# Blues_Brkr.net
KiCad netlist of a schematic drawn in Altium Designer
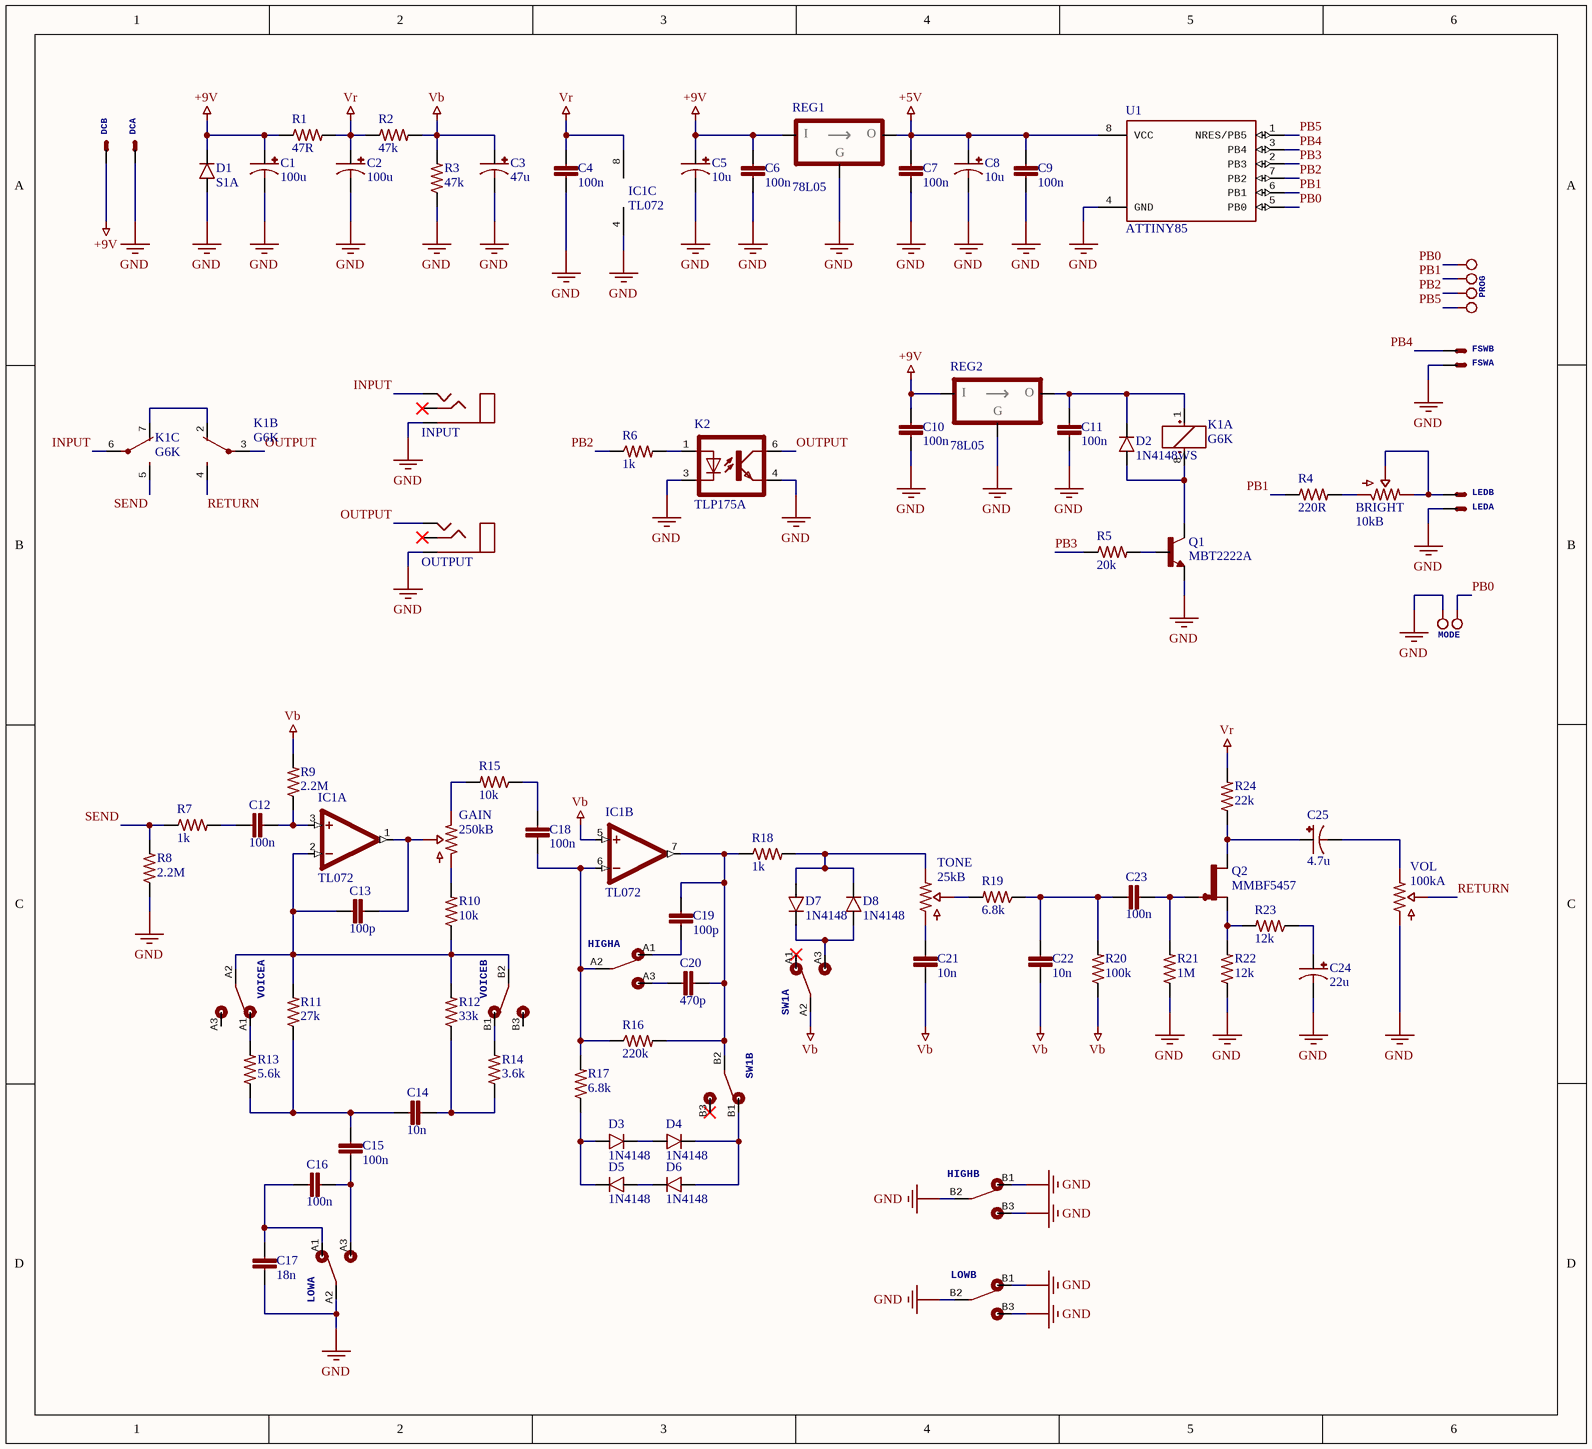
[diagram p0: Blues Brkr.SchDoc]

(export (version "E")
  (design (tool "Eeschema 10.0.6"))
  (components
    (comp (ref "BRIGHT")
      (value "10kB")
      (footprint "BOURNS_3362P")
      (description "10k Lin 3362P trimmer")
      (libsource (lib "Pedals") (part "TRIM_10kB_3362P"))
    )
    (comp (ref "C1")
      (value "100u")
      (footprint "CAPAE_D")
      (description "CAP ALUM 100UF 25V SMD")
      (fields
        (field (name "MANUFACTURER") "Multicomp")
        (field (name "MANUFACTURER PART NUMBER") "MCVVT025M101EA6L")
      )
      (libsource (lib "Pedals SMD") (part "MCVVT025M101EA6L"))
    )
    (comp (ref "C2")
      (value "100u")
      (footprint "CAPAE_D")
      (description "CAP ALUM 100UF 25V SMD")
      (fields
        (field (name "MANUFACTURER") "Multicomp")
        (field (name "MANUFACTURER PART NUMBER") "MCVVT025M101EA6L")
      )
      (libsource (lib "Pedals SMD") (part "MCVVT025M101EA6L"))
    )
    (comp (ref "C3")
      (value "47u")
      (footprint "CAPAE_D")
      (description "CAP ALUM 47UF 25V SMD")
      (fields
        (field (name "MANUFACTURER") "Multicomp")
        (field (name "MANUFACTURER PART NUMBER") "MCVVT025M470EA1L")
      )
      (libsource (lib "Pedals SMD") (part "MCVVT025M470EA1L"))
    )
    (comp (ref "C4")
      (value "100n")
      (footprint "CHIP_0603")
      (description "CAP CER 100NF 50V X7R 0603")
      (fields
        (field (name "MANUFACTURER") "Multicomp")
        (field (name "MANUFACTURER PART NUMBER") "MC0603B104K500CT")
      )
      (libsource (lib "Pedals SMD") (part "MC0603B104K500CT"))
    )
    (comp (ref "C5")
      (value "10u")
      (footprint "CAPAE_B")
      (description "CAP ALUM 10UF 25V SMD")
      (fields
        (field (name "MANUFACTURER") "Multicomp")
        (field (name "MANUFACTURER PART NUMBER") "MCVVT025M100CA1L")
      )
      (libsource (lib "Pedals SMD") (part "MCVVT025M100CA1L"))
    )
    (comp (ref "C6")
      (value "100n")
      (footprint "CHIP_0603")
      (description "CAP CER 100NF 50V X7R 0603")
      (fields
        (field (name "MANUFACTURER") "Multicomp")
        (field (name "MANUFACTURER PART NUMBER") "MC0603B104K500CT")
      )
      (libsource (lib "Pedals SMD") (part "MC0603B104K500CT"))
    )
    (comp (ref "C7")
      (value "100n")
      (footprint "CHIP_0603")
      (description "CAP CER 100NF 50V X7R 0603")
      (fields
        (field (name "MANUFACTURER") "Multicomp")
        (field (name "MANUFACTURER PART NUMBER") "MC0603B104K500CT")
      )
      (libsource (lib "Pedals SMD") (part "MC0603B104K500CT"))
    )
    (comp (ref "C8")
      (value "10u")
      (footprint "CAPAE_B")
      (description "CAP ALUM 10UF 25V SMD")
      (fields
        (field (name "MANUFACTURER") "Multicomp")
        (field (name "MANUFACTURER PART NUMBER") "MCVVT025M100CA1L")
      )
      (libsource (lib "Pedals SMD") (part "MCVVT025M100CA1L"))
    )
    (comp (ref "C9")
      (value "100n")
      (footprint "CHIP_0603")
      (description "CAP CER 100NF 50V X7R 0603")
      (fields
        (field (name "MANUFACTURER") "Multicomp")
        (field (name "MANUFACTURER PART NUMBER") "MC0603B104K500CT")
      )
      (libsource (lib "Pedals SMD") (part "MC0603B104K500CT"))
    )
    (comp (ref "C10")
      (value "100n")
      (footprint "CHIP_0603")
      (description "CAP CER 100NF 50V X7R 0603")
      (fields
        (field (name "MANUFACTURER") "Multicomp")
        (field (name "MANUFACTURER PART NUMBER") "MC0603B104K500CT")
      )
      (libsource (lib "Pedals SMD") (part "MC0603B104K500CT"))
    )
    (comp (ref "C11")
      (value "100n")
      (footprint "CHIP_0603")
      (description "CAP CER 100NF 50V X7R 0603")
      (fields
        (field (name "MANUFACTURER") "Multicomp")
        (field (name "MANUFACTURER PART NUMBER") "MC0603B104K500CT")
      )
      (libsource (lib "Pedals SMD") (part "MC0603B104K500CT"))
    )
    (comp (ref "C12")
      (value "100n")
      (footprint "CHIP_1206")
      (description "CAP CER 100NF 50V C0G/NP0 1206")
      (fields
        (field (name "MANUFACTURER") "Murata")
        (field (name "MANUFACTURER PART NUMBER") "GRM31C5C1H104JA01L")
      )
      (libsource (lib "Pedals SMD") (part "GRM31C5C1H104JA01L"))
    )
    (comp (ref "C13")
      (value "100p")
      (footprint "CHIP_0603")
      (description "CAP CER 100PF 50V C0G/NP0 0603")
      (fields
        (field (name "MANUFACTURER") "Multicomp")
        (field (name "MANUFACTURER PART NUMBER") "MC0603N101J500CT")
      )
      (libsource (lib "") (part "MC0603N101J500CT_1"))
    )
    (comp (ref "C14")
      (value "10n")
      (footprint "CHIP_0603")
      (description "CAP CER 10NF 50V C0G/NP0 0603")
      (fields
        (field (name "MANUFACTURER") "Murata")
        (field (name "MANUFACTURER PART NUMBER") "GRM1885C1H103JA01D")
      )
      (libsource (lib "Pedals SMD") (part "GRM1885C1H103JA01D"))
    )
    (comp (ref "C15")
      (value "100n")
      (footprint "CHIP_1206")
      (description "CAP CER 100NF 50V C0G/NP0 1206")
      (fields
        (field (name "MANUFACTURER") "Murata")
        (field (name "MANUFACTURER PART NUMBER") "GRM31C5C1H104JA01L")
      )
      (libsource (lib "") (part "GRM31C5C1H104JA01L_1"))
    )
    (comp (ref "C16")
      (value "100n")
      (footprint "CHIP_1206")
      (description "CAP CER 100NF 50V C0G/NP0 1206")
      (fields
        (field (name "MANUFACTURER") "Murata")
        (field (name "MANUFACTURER PART NUMBER") "GRM31C5C1H104JA01L")
      )
      (libsource (lib "") (part "GRM31C5C1H104JA01L_2"))
    )
    (comp (ref "C17")
      (value "18n")
      (footprint "CHIP_0805")
      (description "CAP CER 18NF 50V C0G/NP0 0805")
      (fields
        (field (name "MANUFACTURER") "Murata")
        (field (name "MANUFACTURER PART NUMBER") "GRM21B5C1H183JA01L")
      )
      (libsource (lib "Pedals SMD") (part "GRM21B5C1H183JA01L"))
    )
    (comp (ref "C18")
      (value "100n")
      (footprint "CHIP_1206")
      (description "CAP CER 100NF 50V C0G/NP0 1206")
      (fields
        (field (name "MANUFACTURER") "Murata")
        (field (name "MANUFACTURER PART NUMBER") "GRM31C5C1H104JA01L")
      )
      (libsource (lib "") (part "GRM31C5C1H104JA01L_1"))
    )
    (comp (ref "C19")
      (value "100p")
      (footprint "CHIP_0603")
      (description "CAP CER 100PF 50V C0G/NP0 0603")
      (fields
        (field (name "MANUFACTURER") "Multicomp")
        (field (name "MANUFACTURER PART NUMBER") "MC0603N101J500CT")
      )
      (libsource (lib "Pedals SMD") (part "MC0603N101J500CT"))
    )
    (comp (ref "C20")
      (value "470p")
      (footprint "CHIP_0603")
      (description "CAP CER 470PF 50V C0G/NP0 0603")
      (fields
        (field (name "MANUFACTURER") "Multicomp")
        (field (name "MANUFACTURER PART NUMBER") "MC0603N471J500CT")
      )
      (libsource (lib "Pedals SMD") (part "MC0603N471J500CT"))
    )
    (comp (ref "C21")
      (value "10n")
      (footprint "CHIP_0603")
      (description "CAP CER 10NF 50V C0G/NP0 0603")
      (fields
        (field (name "MANUFACTURER") "Murata")
        (field (name "MANUFACTURER PART NUMBER") "GRM1885C1H103JA01D")
      )
      (libsource (lib "") (part "GRM1885C1H103JA01D_1"))
    )
    (comp (ref "C22")
      (value "10n")
      (footprint "CHIP_0603")
      (description "CAP CER 10NF 50V C0G/NP0 0603")
      (fields
        (field (name "MANUFACTURER") "Murata")
        (field (name "MANUFACTURER PART NUMBER") "GRM1885C1H103JA01D")
      )
      (libsource (lib "") (part "GRM1885C1H103JA01D_1"))
    )
    (comp (ref "C23")
      (value "100n")
      (footprint "CHIP_1206")
      (description "CAP CER 100NF 50V C0G/NP0 1206")
      (fields
        (field (name "MANUFACTURER") "Murata")
        (field (name "MANUFACTURER PART NUMBER") "GRM31C5C1H104JA01L")
      )
      (libsource (lib "Pedals SMD") (part "GRM31C5C1H104JA01L"))
    )
    (comp (ref "C24")
      (value "22u")
      (footprint "CAPAE_D")
      (description "CAP ALUM 22UF 20% 35V LESR SMD")
      (fields
        (field (name "MANUFACTURER") "Panasonic")
        (field (name "MANUFACTURER PART NUMBER") "EEEFC1V220AP")
      )
      (libsource (lib "Pedals SMD") (part "EEEFC1V220AP"))
    )
    (comp (ref "C25")
      (value "4.7u")
      (footprint "CAPAE_C")
      (description "CAP ALUM 4.7UF 50V LESR SMD")
      (fields
        (field (name "MANUFACTURER") "Panasonic")
        (field (name "MANUFACTURER PART NUMBER") "EEEFC1H4R7R")
      )
      (libsource (lib "Pedals SMD") (part "EEEFC1H4R7R"))
    )
    (comp (ref "D1")
      (value "S1A")
      (footprint "DO214")
      (description "DIODE GEN PURP 50V 1A SMA")
      (fields (field (name "MANUFACTURER") "ON Semiconductor / Fairchild"))
      (libsource (lib "Pedals SMD") (part "S1A"))
    )
    (comp (ref "D2")
      (value "1N4148WS")
      (footprint "SOD323")
      (description "DIODE GEN PURP 75V 150MA SOD323F")
      (fields (field (name "MANUFACTURER") "ON Semiconductor / Fairchild"))
      (libsource (lib "Pedals SMD") (part "1N4148WS"))
    )
    (comp (ref "D3") (value "1N4148") (footprint "DO35_2") (libsource (lib "Pedals") (part "D_1N4148")))
    (comp (ref "D4") (value "1N4148") (footprint "DO35_2") (libsource (lib "Pedals") (part "D_1N4148")))
    (comp (ref "D5") (value "1N4148") (footprint "DO35_2") (libsource (lib "Pedals") (part "D_1N4148")))
    (comp (ref "D6") (value "1N4148") (footprint "DO35_2") (libsource (lib "Pedals") (part "D_1N4148")))
    (comp (ref "D7") (value "1N4148") (footprint "DO35_2") (libsource (lib "Pedals") (part "D_1N4148")))
    (comp (ref "D8") (value "1N4148") (footprint "DO35_2") (libsource (lib "Pedals") (part "D_1N4148")))
    (comp (ref "DC")
      (value "J_JST-XH-02")
      (footprint "JST-XH-02")
      (description "2 Pins male XH header")
      (libsource (lib "Pedals") (part "J_JST-XH-02"))
    )
    (comp (ref "FSW")
      (value "~")
      (footprint "JST-XH-02")
      (description "2 Pins male XH header")
      (libsource (lib "Pedals") (part "JST-XH-02"))
    )
    (comp (ref "GAIN")
      (value "250kB")
      (footprint "ALPHA_16mm_BOTTOM")
      (description "250k Lin potentiometer round shaft")
      (libsource (lib "Pedals") (part "250kB_ALPHA_16mm"))
    )
    (comp (ref "HIGH")
      (value "DPDT")
      (footprint "DPDT_SLIDE")
      (description "DPDT slide switch ON/OFF/ON")
      (libsource (lib "Pedals") (part "SW_SLIDE_DPDT_ON-OFF-ON"))
    )
    (comp (ref "IC1")
      (value "TL072")
      (footprint "SO-8")
      (description "IC OPAMP JFET 4MHZ 8SO")
      (fields
        (field (name "MANUFACTURER") "STMicroelectronics")
        (field (name "MANUFACTURER PART NUMBER") "TL072CDT")
      )
      (libsource (lib "Pedals SMD") (part "TL072CDT"))
    )
    (comp (ref "INPUT")
      (value "~")
      (footprint "STEREO")
      (description "6.35mm stereo insulated socket jack PCB mounted")
      (libsource (lib "Pedals") (part "STEREO"))
    )
    (comp (ref "K1")
      (value "G6K")
      (footprint "G6K")
      (description "OMRON - G6K-2F 5DC - RELAY, SIGNAL, DPDT, 30VDC, 1A")
      (fields (field (name "MANUFACTURER") "Cliff") (field (name "MANUFACTURER PART NUMBER") "G6K-2F5DC"))
      (libsource (lib "Pedals SMD") (part "G6K-2F5DC"))
    )
    (comp (ref "K2")
      (value "TLP175A")
      (footprint "TLP175A")
      (description "Toshiba TLP175A AC Input MOSFET Output Optocoupler, Surface Mount, 4-Pin SOIC")
      (fields (field (name "MANUFACTURER") "Toshiba"))
      (libsource (lib "Pedals SMD") (part "TLP175A"))
    )
    (comp (ref "LED")
      (value "~")
      (footprint "JST-XH-02")
      (description "2 Pins male XH header")
      (libsource (lib "Pedals") (part "JST-XH-02"))
    )
    (comp (ref "LOW")
      (value "DPDT")
      (footprint "DPDT_SLIDE")
      (description "DPDT slide switch ON/OFF/ON")
      (libsource (lib "Pedals") (part "SW_SLIDE_DPDT_ON-OFF-ON"))
    )
    (comp (ref "MODE")
      (value "HEADER_2PINS")
      (footprint "HEADER_2PINS")
      (description "2 Pins male header")
      (libsource (lib "Pedals") (part "HEADER_2PINS"))
    )
    (comp (ref "OUTPUT")
      (value "~")
      (footprint "STEREO")
      (description "6.35mm stereo insulated socket jack PCB mounted")
      (libsource (lib "Pedals") (part "STEREO"))
    )
    (comp (ref "PROG")
      (value "J_HEADER_4PINS_FEM")
      (footprint "HEADER_4Pins_FEM")
      (description "4 Pins female header")
      (libsource (lib "Pedals") (part "J_HEADER_4PINS_FEM"))
    )
    (comp (ref "Q1")
      (value "MBT2222A")
      (footprint "SOT323")
      (description "TRANS NPN 40V 0.6A SOT323")
      (fields
        (field (name "MANUFACTURER") "ON Semiconductor")
        (field (name "MANUFACTURER PART NUMBER") "MMBT2222AWT1G")
      )
      (libsource (lib "Pedals SMD") (part "MMBT2222AWT1G"))
    )
    (comp (ref "Q2")
      (value "MMBF5457")
      (footprint "SOT23")
      (description "JFET N-CH 25V 350MW SOT23")
      (fields (field (name "MANUFACTURER") "ON Semiconductor / Fairchild"))
      (libsource (lib "Pedals SMD") (part "MMBF5457"))
    )
    (comp (ref "R1")
      (value "47R")
      (footprint "CHIP_R_1206")
      (description "RES SMD 47 OHM 1% 1/4W 1206")
      (fields
        (field (name "MANUFACTURER") "Vishay")
        (field (name "MANUFACTURER PART NUMBER") "CRCW120647R0FKEA")
      )
      (libsource (lib "Pedals SMD") (part "CRCW120647R0FKEA"))
    )
    (comp (ref "R2")
      (value "47k")
      (footprint "CHIP_R_1206")
      (description "RES SMD 47K OHM 1% 1/4W 1206")
      (fields
        (field (name "MANUFACTURER") "Vishay")
        (field (name "MANUFACTURER PART NUMBER") "CRCW120647K0FKEA")
      )
      (libsource (lib "Pedals SMD") (part "CRCW120647K0FKEA"))
    )
    (comp (ref "R3")
      (value "47k")
      (footprint "CHIP_R_1206")
      (description "RES SMD 47K OHM 1% 1/4W 1206")
      (fields
        (field (name "MANUFACTURER") "Vishay")
        (field (name "MANUFACTURER PART NUMBER") "CRCW120647K0FKEA")
      )
      (libsource (lib "Pedals SMD") (part "CRCW120647K0FKEA"))
    )
    (comp (ref "R4")
      (value "220R")
      (footprint "CHIP_R_1206")
      (description "RES SMD 220 OHM 1% 1/4W 1206")
      (fields
        (field (name "MANUFACTURER") "Vishay")
        (field (name "MANUFACTURER PART NUMBER") "CRCW1206220RFKEA")
      )
      (libsource (lib "Pedals SMD") (part "CRCW1206220RFKEA"))
    )
    (comp (ref "R5")
      (value "20k")
      (footprint "CHIP_R_0603")
      (description "RES SMD 20K OHM 1% 1/10W 0603")
      (fields
        (field (name "MANUFACTURER") "Vishay")
        (field (name "MANUFACTURER PART NUMBER") "CRCW060320K0FKEA")
      )
      (libsource (lib "Pedals SMD") (part "CRCW060320K0FKEA"))
    )
    (comp (ref "R6")
      (value "1k")
      (footprint "CHIP_R_0603")
      (description "RES SMD 1K OHM 1% 1/10W 0603")
      (fields
        (field (name "MANUFACTURER") "Vishay Dale")
        (field (name "MANUFACTURER PART NUMBER") "CRCW06031K00FKEA")
      )
      (libsource (lib "Pedals SMD") (part "CRCW06031K00FKEA"))
    )
    (comp (ref "R7")
      (value "1k")
      (footprint "CHIP_R_0603")
      (description "RES SMD 1K OHM 1% 1/10W 0603")
      (fields
        (field (name "MANUFACTURER") "Vishay Dale")
        (field (name "MANUFACTURER PART NUMBER") "CRCW06031K00FKEA")
      )
      (libsource (lib "Pedals SMD") (part "CRCW06031K00FKEA"))
    )
    (comp (ref "R8")
      (value "2.2M")
      (footprint "CHIP_R_0603")
      (description "RES SMD 2.2M OHM 1% 1/10W 0603")
      (fields
        (field (name "MANUFACTURER") "Vishay")
        (field (name "MANUFACTURER PART NUMBER") "CRCW06032M20FKEA")
      )
      (libsource (lib "Pedals SMD") (part "CRCW06032M20FKEA"))
    )
    (comp (ref "R9")
      (value "2.2M")
      (footprint "CHIP_R_0603")
      (description "RES SMD 2.2M OHM 1% 1/10W 0603")
      (fields
        (field (name "MANUFACTURER") "Vishay")
        (field (name "MANUFACTURER PART NUMBER") "CRCW06032M20FKEA")
      )
      (libsource (lib "Pedals SMD") (part "CRCW06032M20FKEA"))
    )
    (comp (ref "R10")
      (value "10k")
      (footprint "CHIP_R_0603")
      (description "RES SMD 10K OHM 1% 1/10W 0603")
      (fields
        (field (name "MANUFACTURER") "Vishay")
        (field (name "MANUFACTURER PART NUMBER") "CRCW060310K0FKEA")
      )
      (libsource (lib "Pedals SMD") (part "CRCW060310K0FKEA"))
    )
    (comp (ref "R11")
      (value "27k")
      (footprint "CHIP_R_0603")
      (description "RES SMD 27K OHM 1% 1/10W 0603")
      (fields
        (field (name "MANUFACTURER") "Vishay")
        (field (name "MANUFACTURER PART NUMBER") "CRCW060327K0FKEA")
      )
      (libsource (lib "Pedals SMD") (part "CRCW060327K0FKEA"))
    )
    (comp (ref "R12")
      (value "33k")
      (footprint "CHIP_R_0603")
      (description "RES SMD 33K OHM 1% 1/10W 0603")
      (fields
        (field (name "MANUFACTURER") "Vishay")
        (field (name "MANUFACTURER PART NUMBER") "CRCW060333K0FKEA")
      )
      (libsource (lib "Pedals SMD") (part "CRCW060333K0FKEA"))
    )
    (comp (ref "R13")
      (value "5.6k")
      (footprint "CHIP_R_0603")
      (description "RES SMD 5.6K OHM 1% 1/10W 0603")
      (fields
        (field (name "MANUFACTURER") "Vishay")
        (field (name "MANUFACTURER PART NUMBER") "CRCW06035K60FKEA")
      )
      (libsource (lib "Pedals SMD") (part "CRCW06035K60FKEA"))
    )
    (comp (ref "R14")
      (value "3.6k")
      (footprint "CHIP_R_0603")
      (description "RES SMD 3.6K OHM 1% 1/10W 0603")
      (fields
        (field (name "MANUFACTURER") "Vishay")
        (field (name "MANUFACTURER PART NUMBER") "CRCW06033K60FKEA")
      )
      (libsource (lib "Pedals SMD") (part "CRCW06033K60FKEA"))
    )
    (comp (ref "R15")
      (value "10k")
      (footprint "CHIP_R_0603")
      (description "RES SMD 10K OHM 1% 1/10W 0603")
      (fields
        (field (name "MANUFACTURER") "Vishay")
        (field (name "MANUFACTURER PART NUMBER") "CRCW060310K0FKEA")
      )
      (libsource (lib "Pedals SMD") (part "CRCW060310K0FKEA"))
    )
    (comp (ref "R16")
      (value "220k")
      (footprint "CHIP_R_0603")
      (description "RES SMD 220K OHM 1% 1/10W 0603")
      (fields
        (field (name "MANUFACTURER") "Vishay")
        (field (name "MANUFACTURER PART NUMBER") "CRCW0603220KFKEA")
      )
      (libsource (lib "Pedals SMD") (part "CRCW0603220KFKEA"))
    )
    (comp (ref "R17")
      (value "6.8k")
      (footprint "CHIP_R_0603")
      (description "RES SMD 6.8K OHM 1% 1/10W 0603")
      (fields
        (field (name "MANUFACTURER") "Vishay")
        (field (name "MANUFACTURER PART NUMBER") "CRCW06036K80FKEA")
      )
      (libsource (lib "Pedals SMD") (part "CRCW06036K80FKEA"))
    )
    (comp (ref "R18")
      (value "1k")
      (footprint "CHIP_R_0603")
      (description "RES SMD 1K OHM 1% 1/10W 0603")
      (fields
        (field (name "MANUFACTURER") "Vishay Dale")
        (field (name "MANUFACTURER PART NUMBER") "CRCW06031K00FKEA")
      )
      (libsource (lib "Pedals SMD") (part "CRCW06031K00FKEA"))
    )
    (comp (ref "R19")
      (value "6.8k")
      (footprint "CHIP_R_0603")
      (description "RES SMD 6.8K OHM 1% 1/10W 0603")
      (fields
        (field (name "MANUFACTURER") "Vishay")
        (field (name "MANUFACTURER PART NUMBER") "CRCW06036K80FKEA")
      )
      (libsource (lib "Pedals SMD") (part "CRCW06036K80FKEA"))
    )
    (comp (ref "R20")
      (value "100k")
      (footprint "CHIP_R_0603")
      (description "RES SMD 100K OHM 1% 1/10W 0603")
      (fields
        (field (name "MANUFACTURER") "Vishay")
        (field (name "MANUFACTURER PART NUMBER") "CRCW0603100KFKEA")
      )
      (libsource (lib "Pedals SMD") (part "CRCW0603100KFKEA"))
    )
    (comp (ref "R21")
      (value "1M")
      (footprint "CHIP_R_0603")
      (description "RES SMD 1M OHM 1% 1/10W 0603")
      (fields
        (field (name "MANUFACTURER") "Vishay")
        (field (name "MANUFACTURER PART NUMBER") "CRCW06031M00FKEA")
      )
      (libsource (lib "Pedals SMD") (part "CRCW06031M00FKEA"))
    )
    (comp (ref "R22")
      (value "12k")
      (footprint "CHIP_R_0603")
      (description "RES SMD 12K OHM 1% 1/10W 0603")
      (fields
        (field (name "MANUFACTURER") "Vishay")
        (field (name "MANUFACTURER PART NUMBER") "CRCW060312K0FKEA")
      )
      (libsource (lib "Pedals SMD") (part "CRCW060312K0FKEA"))
    )
    (comp (ref "R23")
      (value "12k")
      (footprint "CHIP_R_0603")
      (description "RES SMD 12K OHM 1% 1/10W 0603")
      (fields
        (field (name "MANUFACTURER") "Vishay")
        (field (name "MANUFACTURER PART NUMBER") "CRCW060312K0FKEA")
      )
      (libsource (lib "Pedals SMD") (part "CRCW060312K0FKEA"))
    )
    (comp (ref "R24")
      (value "22k")
      (footprint "CHIP_R_0603")
      (description "RES SMD 22K OHM 1% 1/10W 0603")
      (fields
        (field (name "MANUFACTURER") "Vishay")
        (field (name "MANUFACTURER PART NUMBER") "CRCW060322K0FKEA")
      )
      (libsource (lib "Pedals SMD") (part "CRCW060322K0FKEA"))
    )
    (comp (ref "REG1")
      (value "78L05")
      (footprint "SOT23-3")
      (description "TAIWAN SEMICONDUCTOR - TS78L05CX RFG - REG 3-TERMINAL 100MA, SMD, SOT23-3")
      (fields
        (field (name "MANUFACTURER") "Taiwan Semiconductor")
        (field (name "MANUFACTURER PART NUMBER") "TS78L05CXRFG")
      )
      (libsource (lib "Pedals SMD") (part "TS78L05CXRFG"))
    )
    (comp (ref "REG2")
      (value "78L05")
      (footprint "SOT23-3")
      (description "TAIWAN SEMICONDUCTOR - TS78L05CX RFG - REG 3-TERMINAL 100MA, SMD, SOT23-3")
      (fields
        (field (name "MANUFACTURER") "Taiwan Semiconductor")
        (field (name "MANUFACTURER PART NUMBER") "TS78L05CXRFG")
      )
      (libsource (lib "Pedals SMD") (part "TS78L05CXRFG"))
    )
    (comp (ref "SW1")
      (value "DPDT")
      (footprint "DPDT")
      (description "DPDT toggle switch ON/OFF/ON")
      (libsource (lib "Pedals") (part "DPDT_ON-OFF-ON"))
    )
    (comp (ref "TONE")
      (value "25kB")
      (footprint "ALPHA_16mm_BOTTOM")
      (description "25k Lin potentiometer round shaft")
      (libsource (lib "Pedals") (part "25kB_ALPHA_16mm"))
    )
    (comp (ref "U1")
      (value "ATTINY85")
      (footprint "SOP8")
      (description "IC, 8BIT MCU, AVR TINY, 20MHZ, 8-SOIC")
      (fields
        (field (name "MANUFACTURER") "Microchip / Atmel")
        (field (name "MANUFACTURER PART NUMBER") "ATTINY85-20SU")
      )
      (libsource (lib "Pedals SMD") (part "ATTINY85-20SU"))
    )
    (comp (ref "VOICE")
      (value "DPDT")
      (footprint "DPDT_SLIDE")
      (description "DPDT slide switch ON/ON")
      (libsource (lib "") (part "SW_SLIDE_DPDT_ON-ON_1"))
    )
    (comp (ref "VOL")
      (value "100kA")
      (footprint "ALPHA_16mm_BOTTOM")
      (description "100k Log potentiometer round shaft")
      (libsource (lib "Pedals") (part "100kA_ALPHA_16mm"))
    )
  )
  (nets
    (net (code "1") (name "+5V") (class "Default")
      (node (ref "C7") (pin "1") (pinfunction "1_1") (pintype "passive"))
      (node (ref "C8") (pin "+") (pinfunction "+_+") (pintype "passive"))
      (node (ref "C9") (pin "1") (pinfunction "1_1") (pintype "passive"))
      (node (ref "REG1") (pin "1") (pinfunction "OUTPUT_1") (pintype "power_in"))
      (node (ref "U1") (pin "8") (pinfunction "VCC_8") (pintype "power_in"))
    )
    (net (code "2") (name "+9V") (class "Default")
      (node (ref "C1") (pin "+") (pinfunction "+_+") (pintype "passive"))
      (node (ref "C10") (pin "1") (pinfunction "1_1") (pintype "passive"))
      (node (ref "C5") (pin "+") (pinfunction "+_+") (pintype "passive"))
      (node (ref "C6") (pin "1") (pinfunction "1_1") (pintype "passive"))
      (node (ref "D1") (pin "1") (pinfunction "1_1") (pintype "passive"))
      (node (ref "DC") (pin "1") (pinfunction "S_1") (pintype "passive"))
      (node (ref "R1") (pin "1") (pinfunction "1_1") (pintype "passive"))
      (node (ref "REG1") (pin "2") (pinfunction "INPUT_2") (pintype "power_in"))
      (node (ref "REG2") (pin "2") (pinfunction "INPUT_2") (pintype "power_in"))
    )
    (net (code "3") (name "/INPUT") (class "Default")
      (node (ref "INPUT") (pin "T") (pinfunction "T_T") (pintype "passive"))
      (node (ref "K1") (pin "6") (pinfunction "P_6") (pintype "passive"))
    )
    (net (code "4") (name "/OUTPUT") (class "Default")
      (node (ref "K1") (pin "3") (pinfunction "P_3") (pintype "passive"))
      (node (ref "K2") (pin "6") (pinfunction "COL_6") (pintype "passive"))
      (node (ref "OUTPUT") (pin "T") (pinfunction "T_T") (pintype "passive"))
    )
    (net (code "5") (name "/PB0") (class "Default")
      (node (ref "MODE") (pin "2") (pinfunction "2_2") (pintype "passive"))
      (node (ref "PROG") (pin "4") (pinfunction "4_4") (pintype "passive"))
      (node (ref "U1") (pin "5") (pinfunction "PB0_5") (pintype "bidirectional"))
    )
    (net (code "6") (name "/PB1") (class "Default")
      (node (ref "PROG") (pin "3") (pinfunction "3_3") (pintype "passive"))
      (node (ref "R4") (pin "1") (pinfunction "1_1") (pintype "passive"))
      (node (ref "U1") (pin "6") (pinfunction "PB1_6") (pintype "bidirectional"))
    )
    (net (code "7") (name "/PB2") (class "Default")
      (node (ref "PROG") (pin "2") (pinfunction "2_2") (pintype "passive"))
      (node (ref "R6") (pin "1") (pinfunction "1_1") (pintype "passive"))
      (node (ref "U1") (pin "7") (pinfunction "PB2_7") (pintype "bidirectional"))
    )
    (net (code "8") (name "/PB3") (class "Default")
      (node (ref "R5") (pin "1") (pinfunction "1_1") (pintype "passive"))
      (node (ref "U1") (pin "2") (pinfunction "PB3_2") (pintype "bidirectional"))
    )
    (net (code "9") (name "/PB4") (class "Default")
      (node (ref "FSW") (pin "1") (pinfunction "S_1") (pintype "passive"))
      (node (ref "U1") (pin "3") (pinfunction "PB4_3") (pintype "bidirectional"))
    )
    (net (code "10") (name "/PB5") (class "Default")
      (node (ref "PROG") (pin "1") (pinfunction "1_1") (pintype "passive"))
      (node (ref "U1") (pin "1") (pinfunction "NRES/PB5_1") (pintype "bidirectional"))
    )
    (net (code "11") (name "/RETURN") (class "Default")
      (node (ref "K1") (pin "4") (pinfunction "S_4") (pintype "passive"))
      (node (ref "VOL") (pin "2") (pinfunction "2_2") (pintype "passive"))
    )
    (net (code "12") (name "/SEND") (class "Default")
      (node (ref "K1") (pin "5") (pinfunction "S_5") (pintype "passive"))
      (node (ref "R7") (pin "1") (pinfunction "1_1") (pintype "passive"))
      (node (ref "R8") (pin "2") (pinfunction "2_2") (pintype "passive"))
    )
    (net (code "13") (name "GND") (class "Default")
      (node (ref "C1") (pin "-") (pinfunction "-_-") (pintype "passive"))
      (node (ref "C10") (pin "2") (pinfunction "2_2") (pintype "passive"))
      (node (ref "C11") (pin "2") (pinfunction "2_2") (pintype "passive"))
      (node (ref "C17") (pin "2") (pinfunction "2_2") (pintype "passive"))
      (node (ref "C2") (pin "-") (pinfunction "-_-") (pintype "passive"))
      (node (ref "C24") (pin "-") (pinfunction "-_-") (pintype "passive"))
      (node (ref "C3") (pin "-") (pinfunction "-_-") (pintype "passive"))
      (node (ref "C4") (pin "2") (pinfunction "2_2") (pintype "passive"))
      (node (ref "C5") (pin "-") (pinfunction "-_-") (pintype "passive"))
      (node (ref "C6") (pin "2") (pinfunction "2_2") (pintype "passive"))
      (node (ref "C7") (pin "2") (pinfunction "2_2") (pintype "passive"))
      (node (ref "C8") (pin "-") (pinfunction "-_-") (pintype "passive"))
      (node (ref "C9") (pin "2") (pinfunction "2_2") (pintype "passive"))
      (node (ref "D1") (pin "2") (pinfunction "2_2") (pintype "passive"))
      (node (ref "DC") (pin "2") (pinfunction "S_2") (pintype "passive"))
      (node (ref "FSW") (pin "2") (pinfunction "S_2") (pintype "passive"))
      (node (ref "HIGH") (pin "B1") (pinfunction "1_B1") (pintype "passive"))
      (node (ref "HIGH") (pin "B2") (pinfunction "2_B2") (pintype "passive"))
      (node (ref "HIGH") (pin "B3") (pinfunction "3_B3") (pintype "passive"))
      (node (ref "IC1") (pin "4") (pinfunction "V-_4") (pintype "power_in"))
      (node (ref "INPUT") (pin "S") (pinfunction "S_S") (pintype "passive"))
      (node (ref "K2") (pin "3") (pinfunction "C_3") (pintype "passive"))
      (node (ref "K2") (pin "4") (pinfunction "EMIT_4") (pintype "passive"))
      (node (ref "LED") (pin "2") (pinfunction "S_2") (pintype "passive"))
      (node (ref "LOW") (pin "A2") (pinfunction "2_A2") (pintype "passive"))
      (node (ref "LOW") (pin "B1") (pinfunction "1_B1") (pintype "passive"))
      (node (ref "LOW") (pin "B2") (pinfunction "2_B2") (pintype "passive"))
      (node (ref "LOW") (pin "B3") (pinfunction "3_B3") (pintype "passive"))
      (node (ref "MODE") (pin "1") (pinfunction "1_1") (pintype "passive"))
      (node (ref "OUTPUT") (pin "S") (pinfunction "S_S") (pintype "passive"))
      (node (ref "Q1") (pin "2") (pinfunction "E_2") (pintype "passive"))
      (node (ref "R21") (pin "1") (pinfunction "1_1") (pintype "passive"))
      (node (ref "R22") (pin "1") (pinfunction "1_1") (pintype "passive"))
      (node (ref "R3") (pin "1") (pinfunction "1_1") (pintype "passive"))
      (node (ref "R8") (pin "1") (pinfunction "1_1") (pintype "passive"))
      (node (ref "REG1") (pin "3") (pinfunction "COMMON_3") (pintype "power_in"))
      (node (ref "REG2") (pin "3") (pinfunction "COMMON_3") (pintype "power_in"))
      (node (ref "U1") (pin "4") (pinfunction "GND_4") (pintype "power_in"))
      (node (ref "VOL") (pin "1") (pinfunction "1_1") (pintype "passive"))
    )
    (net (code "14") (name "Net-(BRIGHT-Pad1)") (class "Default")
      (node (ref "BRIGHT") (pin "1") (pinfunction "1_1") (pintype "passive"))
      (node (ref "R4") (pin "2") (pinfunction "2_2") (pintype "passive"))
    )
    (net (code "15") (name "Net-(C12-Pad2)") (class "Default")
      (node (ref "C12") (pin "2") (pinfunction "2_2") (pintype "passive"))
      (node (ref "R7") (pin "2") (pinfunction "2_2") (pintype "passive"))
    )
    (net (code "16") (name "Net-(C14-Pad1)") (class "Default")
      (node (ref "C14") (pin "1") (pinfunction "1_1") (pintype "passive"))
      (node (ref "R12") (pin "1") (pinfunction "1_1") (pintype "passive"))
      (node (ref "R14") (pin "1") (pinfunction "1_1") (pintype "passive"))
    )
    (net (code "17") (name "Net-(C14-Pad2)") (class "Default")
      (node (ref "C14") (pin "2") (pinfunction "2_2") (pintype "passive"))
      (node (ref "C15") (pin "1") (pinfunction "1_1") (pintype "passive"))
      (node (ref "R11") (pin "1") (pinfunction "1_1") (pintype "passive"))
      (node (ref "R13") (pin "1") (pinfunction "1_1") (pintype "passive"))
    )
    (net (code "18") (name "Net-(C18-Pad1)") (class "Default")
      (node (ref "C18") (pin "1") (pinfunction "1_1") (pintype "passive"))
      (node (ref "R15") (pin "1") (pinfunction "1_1") (pintype "passive"))
    )
    (net (code "19") (name "Net-(C21-Pad1)") (class "Default")
      (node (ref "C21") (pin "1") (pinfunction "1_1") (pintype "passive"))
      (node (ref "TONE") (pin "1") (pinfunction "1_1") (pintype "passive"))
    )
    (net (code "20") (name "Net-(C22-Pad1)") (class "Default")
      (node (ref "C22") (pin "1") (pinfunction "1_1") (pintype "passive"))
      (node (ref "C23") (pin "2") (pinfunction "2_2") (pintype "passive"))
      (node (ref "R19") (pin "1") (pinfunction "1_1") (pintype "passive"))
      (node (ref "R20") (pin "2") (pinfunction "2_2") (pintype "passive"))
    )
    (net (code "21") (name "Net-(C24-Pad+)") (class "Default")
      (node (ref "C24") (pin "+") (pinfunction "+_+") (pintype "passive"))
      (node (ref "R23") (pin "1") (pinfunction "1_1") (pintype "passive"))
    )
    (net (code "22") (name "Net-(C25-Pad-)") (class "Default")
      (node (ref "C25") (pin "-") (pinfunction "-_-") (pintype "passive"))
      (node (ref "VOL") (pin "3") (pinfunction "3_3") (pintype "passive"))
    )
    (net (code "23") (name "Net-(D3-PadA)") (class "Default")
      (node (ref "D3") (pin "A") (pinfunction "A_A") (pintype "passive"))
      (node (ref "D5") (pin "C") (pinfunction "C_C") (pintype "passive"))
      (node (ref "R17") (pin "1") (pinfunction "1_1") (pintype "passive"))
    )
    (net (code "24") (name "Net-(D3-PadC)") (class "Default")
      (node (ref "D3") (pin "C") (pinfunction "C_C") (pintype "passive"))
      (node (ref "D4") (pin "A") (pinfunction "A_A") (pintype "passive"))
    )
    (net (code "25") (name "Net-(D5-PadA)") (class "Default")
      (node (ref "D5") (pin "A") (pinfunction "A_A") (pintype "passive"))
      (node (ref "D6") (pin "C") (pinfunction "C_C") (pintype "passive"))
    )
    (net (code "26") (name "Net-(D7-PadA)") (class "Default")
      (node (ref "D7") (pin "A") (pinfunction "A_A") (pintype "passive"))
      (node (ref "D8") (pin "C") (pinfunction "C_C") (pintype "passive"))
      (node (ref "R18") (pin "2") (pinfunction "2_2") (pintype "passive"))
      (node (ref "TONE") (pin "3") (pinfunction "3_3") (pintype "passive"))
    )
    (net (code "27") (name "Net-(GAIN-Pad1)") (class "Default")
      (node (ref "GAIN") (pin "1") (pinfunction "1_1") (pintype "passive"))
      (node (ref "R10") (pin "2") (pinfunction "2_2") (pintype "passive"))
    )
    (net (code "28") (name "Net-(GAIN-Pad3)") (class "Default")
      (node (ref "GAIN") (pin "3") (pinfunction "3_3") (pintype "passive"))
      (node (ref "R15") (pin "2") (pinfunction "2_2") (pintype "passive"))
    )
    (net (code "29") (name "Net-(HIGHA-1)") (class "Default")
      (node (ref "C19") (pin "2") (pinfunction "2_2") (pintype "passive"))
      (node (ref "HIGH") (pin "A1") (pinfunction "1_A1") (pintype "passive"))
    )
    (net (code "30") (name "Net-(HIGHA-2)") (class "Default")
      (node (ref "C18") (pin "2") (pinfunction "2_2") (pintype "passive"))
      (node (ref "HIGH") (pin "A2") (pinfunction "2_A2") (pintype "passive"))
      (node (ref "IC1") (pin "6") (pinfunction "-IN_6") (pintype "input"))
      (node (ref "R16") (pin "1") (pinfunction "1_1") (pintype "passive"))
      (node (ref "R17") (pin "2") (pinfunction "2_2") (pintype "passive"))
    )
    (net (code "31") (name "Net-(HIGHA-3)") (class "Default")
      (node (ref "C20") (pin "2") (pinfunction "2_2") (pintype "passive"))
      (node (ref "HIGH") (pin "A3") (pinfunction "3_A3") (pintype "passive"))
    )
    (net (code "32") (name "Net-(IC1A-+IN)") (class "Default")
      (node (ref "C12") (pin "1") (pinfunction "1_1") (pintype "passive"))
      (node (ref "IC1") (pin "3") (pinfunction "+IN_3") (pintype "input"))
      (node (ref "R9") (pin "1") (pinfunction "1_1") (pintype "passive"))
    )
    (net (code "33") (name "Net-(IC1A--IN)") (class "Default")
      (node (ref "C13") (pin "2") (pinfunction "2_2") (pintype "passive"))
      (node (ref "IC1") (pin "2") (pinfunction "-IN_2") (pintype "input"))
      (node (ref "R10") (pin "1") (pinfunction "1_1") (pintype "passive"))
      (node (ref "R11") (pin "2") (pinfunction "2_2") (pintype "passive"))
      (node (ref "R12") (pin "2") (pinfunction "2_2") (pintype "passive"))
      (node (ref "VOICE") (pin "A2") (pinfunction "2_A2") (pintype "passive"))
      (node (ref "VOICE") (pin "B2") (pinfunction "2_B2") (pintype "passive"))
    )
    (net (code "34") (name "Net-(IC1A-OUT)") (class "Default")
      (node (ref "C13") (pin "1") (pinfunction "1_1") (pintype "passive"))
      (node (ref "GAIN") (pin "2") (pinfunction "2_2") (pintype "passive"))
      (node (ref "IC1") (pin "1") (pinfunction "OUT_1") (pintype "output"))
    )
    (net (code "35") (name "Net-(IC1B-OUT)") (class "Default")
      (node (ref "C19") (pin "1") (pinfunction "1_1") (pintype "passive"))
      (node (ref "C20") (pin "1") (pinfunction "1_1") (pintype "passive"))
      (node (ref "IC1") (pin "7") (pinfunction "OUT_7") (pintype "output"))
      (node (ref "R16") (pin "2") (pinfunction "2_2") (pintype "passive"))
      (node (ref "R18") (pin "1") (pinfunction "1_1") (pintype "passive"))
      (node (ref "SW1") (pin "B2") (pinfunction "2_B2") (pintype "passive"))
    )
    (net (code "36") (name "Net-(K1A-+)") (class "Default")
      (node (ref "C11") (pin "1") (pinfunction "1_1") (pintype "passive"))
      (node (ref "D2") (pin "1") (pinfunction "1_1") (pintype "passive"))
      (node (ref "K1") (pin "1") (pinfunction "+_1") (pintype "passive"))
      (node (ref "REG2") (pin "1") (pinfunction "OUTPUT_1") (pintype "power_in"))
    )
    (net (code "37") (name "Net-(K1A--)") (class "Default")
      (node (ref "D2") (pin "2") (pinfunction "2_2") (pintype "passive"))
      (node (ref "K1") (pin "8") (pinfunction "-_8") (pintype "passive"))
      (node (ref "Q1") (pin "3") (pinfunction "C_3") (pintype "passive"))
    )
    (net (code "38") (name "Net-(K1B-O)") (class "Default")
      (node (ref "K1") (pin "2") (pinfunction "O_2") (pintype "passive"))
      (node (ref "K1") (pin "7") (pinfunction "O_7") (pintype "passive"))
    )
    (net (code "39") (name "Net-(K2-A)") (class "Default")
      (node (ref "K2") (pin "1") (pinfunction "A_1") (pintype "passive"))
      (node (ref "R6") (pin "2") (pinfunction "2_2") (pintype "passive"))
    )
    (net (code "40") (name "Net-(LEDB-S)") (class "Default")
      (node (ref "BRIGHT") (pin "2") (pinfunction "2_2") (pintype "passive"))
      (node (ref "BRIGHT") (pin "3") (pinfunction "3_3") (pintype "passive"))
      (node (ref "LED") (pin "1") (pinfunction "S_1") (pintype "passive"))
    )
    (net (code "41") (name "Net-(LOWA-1)") (class "Default")
      (node (ref "C16") (pin "1") (pinfunction "1_1") (pintype "passive"))
      (node (ref "C17") (pin "1") (pinfunction "1_1") (pintype "passive"))
      (node (ref "LOW") (pin "A1") (pinfunction "1_A1") (pintype "passive"))
    )
    (net (code "42") (name "Net-(LOWA-3)") (class "Default")
      (node (ref "C15") (pin "2") (pinfunction "2_2") (pintype "passive"))
      (node (ref "C16") (pin "2") (pinfunction "2_2") (pintype "passive"))
      (node (ref "LOW") (pin "A3") (pinfunction "3_A3") (pintype "passive"))
    )
    (net (code "43") (name "Net-(Q1-B)") (class "Default")
      (node (ref "Q1") (pin "1") (pinfunction "B_1") (pintype "passive"))
      (node (ref "R5") (pin "2") (pinfunction "2_2") (pintype "passive"))
    )
    (net (code "44") (name "Net-(Q2-D)") (class "Default")
      (node (ref "C25") (pin "+") (pinfunction "+_+") (pintype "passive"))
      (node (ref "Q2") (pin "1") (pinfunction "D_1") (pintype "passive"))
      (node (ref "R24") (pin "1") (pinfunction "1_1") (pintype "passive"))
    )
    (net (code "45") (name "Net-(Q2-G)") (class "Default")
      (node (ref "C23") (pin "1") (pinfunction "1_1") (pintype "passive"))
      (node (ref "Q2") (pin "3") (pinfunction "G_3") (pintype "passive"))
      (node (ref "R21") (pin "2") (pinfunction "2_2") (pintype "passive"))
    )
    (net (code "46") (name "Net-(Q2-S)") (class "Default")
      (node (ref "Q2") (pin "2") (pinfunction "S_2") (pintype "passive"))
      (node (ref "R22") (pin "2") (pinfunction "2_2") (pintype "passive"))
      (node (ref "R23") (pin "2") (pinfunction "2_2") (pintype "passive"))
    )
    (net (code "47") (name "Net-(R19-Pad2)") (class "Default")
      (node (ref "R19") (pin "2") (pinfunction "2_2") (pintype "passive"))
      (node (ref "TONE") (pin "2") (pinfunction "2_2") (pintype "passive"))
    )
    (net (code "48") (name "Net-(SW1A-3)") (class "Default")
      (node (ref "D7") (pin "C") (pinfunction "C_C") (pintype "passive"))
      (node (ref "D8") (pin "A") (pinfunction "A_A") (pintype "passive"))
      (node (ref "SW1") (pin "A3") (pinfunction "3_A3") (pintype "passive"))
    )
    (net (code "49") (name "Net-(SW1B-1)") (class "Default")
      (node (ref "D4") (pin "C") (pinfunction "C_C") (pintype "passive"))
      (node (ref "D6") (pin "A") (pinfunction "A_A") (pintype "passive"))
      (node (ref "SW1") (pin "B1") (pinfunction "1_B1") (pintype "passive"))
    )
    (net (code "50") (name "Net-(VOICEA-1)") (class "Default")
      (node (ref "R13") (pin "2") (pinfunction "2_2") (pintype "passive"))
      (node (ref "VOICE") (pin "A1") (pinfunction "1_A1") (pintype "passive"))
    )
    (net (code "51") (name "Net-(VOICEB-1)") (class "Default")
      (node (ref "R14") (pin "2") (pinfunction "2_2") (pintype "passive"))
      (node (ref "VOICE") (pin "B1") (pinfunction "1_B1") (pintype "passive"))
    )
    (net (code "52") (name "Vb") (class "Default")
      (node (ref "C21") (pin "2") (pinfunction "2_2") (pintype "passive"))
      (node (ref "C22") (pin "2") (pinfunction "2_2") (pintype "passive"))
      (node (ref "C3") (pin "+") (pinfunction "+_+") (pintype "passive"))
      (node (ref "IC1") (pin "5") (pinfunction "+IN_5") (pintype "input"))
      (node (ref "R2") (pin "2") (pinfunction "2_2") (pintype "passive"))
      (node (ref "R20") (pin "1") (pinfunction "1_1") (pintype "passive"))
      (node (ref "R3") (pin "2") (pinfunction "2_2") (pintype "passive"))
      (node (ref "R9") (pin "2") (pinfunction "2_2") (pintype "passive"))
      (node (ref "SW1") (pin "A2") (pinfunction "2_A2") (pintype "passive"))
    )
    (net (code "53") (name "Vr") (class "Default")
      (node (ref "C2") (pin "+") (pinfunction "+_+") (pintype "passive"))
      (node (ref "C4") (pin "1") (pinfunction "1_1") (pintype "passive"))
      (node (ref "IC1") (pin "8") (pinfunction "V+_8") (pintype "power_in"))
      (node (ref "R1") (pin "2") (pinfunction "2_2") (pintype "passive"))
      (node (ref "R2") (pin "1") (pinfunction "1_1") (pintype "passive"))
      (node (ref "R24") (pin "2") (pinfunction "2_2") (pintype "passive"))
    )
    (net (code "54") (name "unconnected-(INPUT-PadR)") (class "Default")
      (node (ref "INPUT") (pin "R") (pinfunction "R_R") (pintype "passive+no_connect"))
    )
    (net (code "55") (name "unconnected-(OUTPUT-PadR)") (class "Default")
      (node (ref "OUTPUT") (pin "R") (pinfunction "R_R") (pintype "passive+no_connect"))
    )
    (net (code "56") (name "unconnected-(SW1A-1-PadA1)") (class "Default")
      (node (ref "SW1") (pin "A1") (pinfunction "1_A1") (pintype "passive+no_connect"))
    )
    (net (code "57") (name "unconnected-(SW1B-3-PadB3)") (class "Default")
      (node (ref "SW1") (pin "B3") (pinfunction "3_B3") (pintype "passive+no_connect"))
    )
    (net (code "58") (name "unconnected-(VOICEA-3-PadA3)") (class "Default")
      (node (ref "VOICE") (pin "A3") (pinfunction "3_A3") (pintype "passive"))
    )
    (net (code "59") (name "unconnected-(VOICEB-3-PadB3)") (class "Default")
      (node (ref "VOICE") (pin "B3") (pinfunction "3_B3") (pintype "passive"))
    )
  )
)
